# MCU.net
KiCad netlist of a schematic drawn in Altium Designer
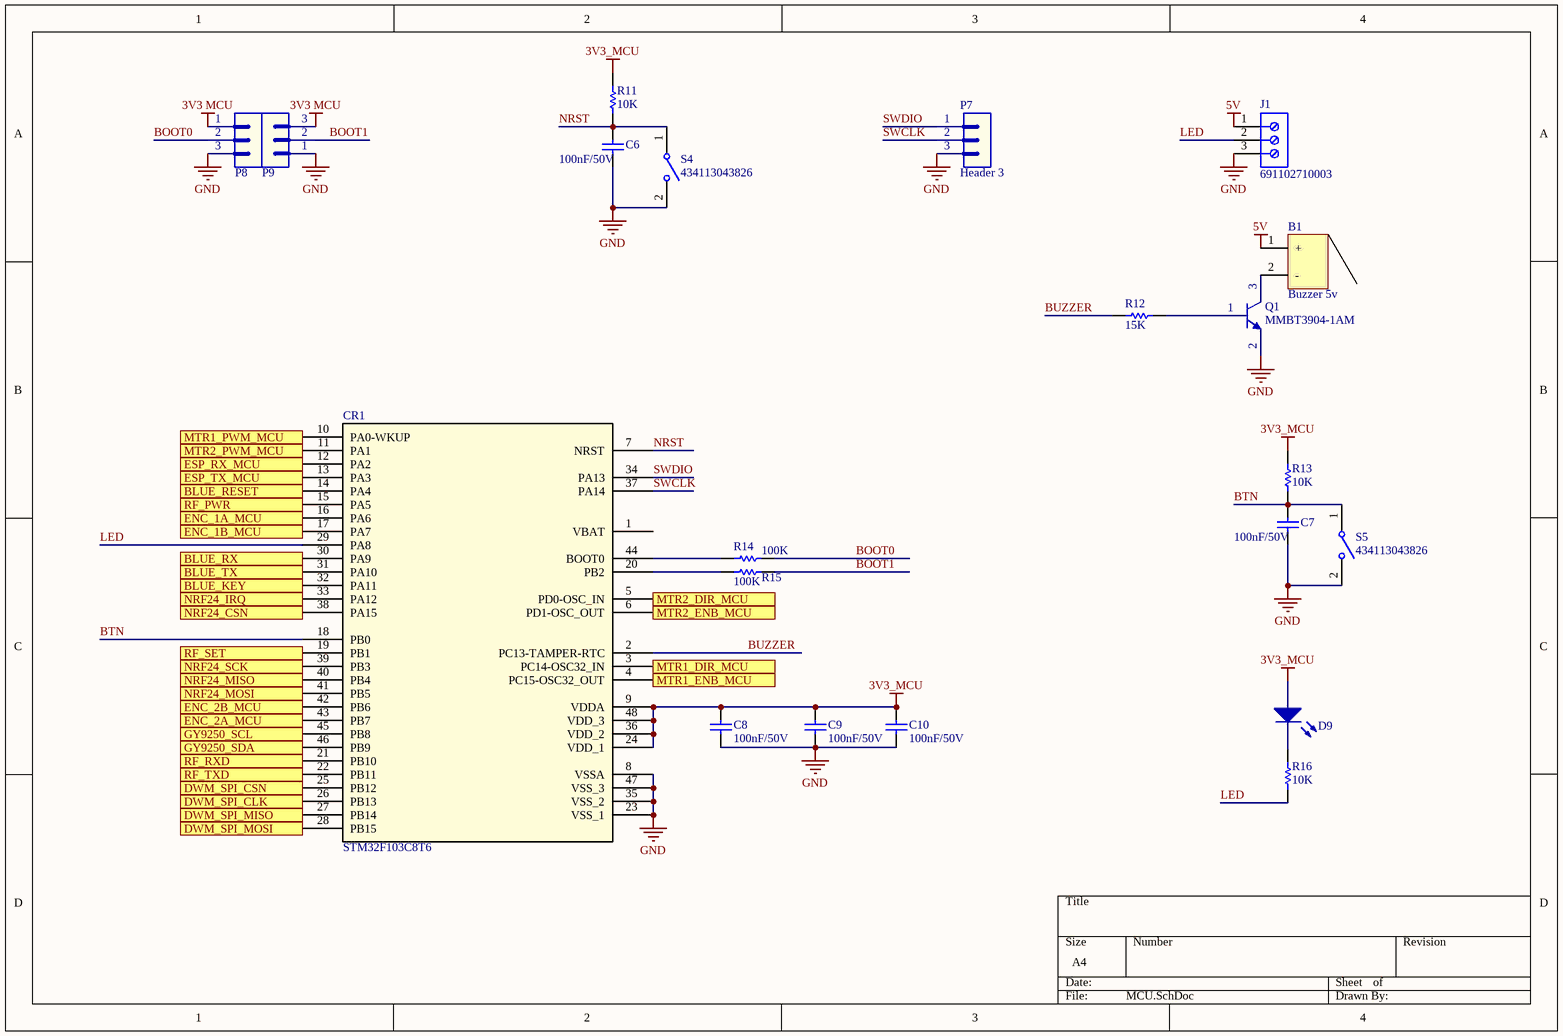
[diagram p0: MCU.SchDoc]

(export (version "E")
  (design (tool "Eeschema 10.0.6"))
  (components
    (comp (ref "B1") (value "Buzzer 5v") (footprint "Buzzer 5v") (libsource (lib "Stm32") (part "Buzzer 5v")))
    (comp (ref "C6")
      (value "100nF/50V")
      (footprint "CAP-SM-0805")
      (description "CAP CER 1000PF 100V X7R 0805")
      (fields
        (field (name "MANUFACTURER") "Johanson Dielectrics Inc.")
        (field (name "MANUFACTURER PART NUMBER") "101X15W102MV4E")
      )
      (libsource (lib "Capacitor") (part "Cap-1nF-50V-0805"))
    )
    (comp (ref "C7")
      (value "100nF/50V")
      (footprint "CAP-SM-0805")
      (description "CAP CER 1000PF 100V X7R 0805")
      (fields
        (field (name "MANUFACTURER") "Johanson Dielectrics Inc.")
        (field (name "MANUFACTURER PART NUMBER") "101X15W102MV4E")
      )
      (libsource (lib "Capacitor") (part "Cap-1nF-50V-0805"))
    )
    (comp (ref "C8")
      (value "100nF/50V")
      (footprint "CAP-SM-0805")
      (description "CAP CER 1000PF 100V X7R 0805")
      (fields
        (field (name "MANUFACTURER") "Johanson Dielectrics Inc.")
        (field (name "MANUFACTURER PART NUMBER") "101X15W102MV4E")
      )
      (libsource (lib "Capacitor") (part "Cap-1nF-50V-0805"))
    )
    (comp (ref "C9")
      (value "100nF/50V")
      (footprint "CAP-SM-0805")
      (description "CAP CER 1000PF 100V X7R 0805")
      (fields
        (field (name "MANUFACTURER") "Johanson Dielectrics Inc.")
        (field (name "MANUFACTURER PART NUMBER") "101X15W102MV4E")
      )
      (libsource (lib "Capacitor") (part "Cap-1nF-50V-0805"))
    )
    (comp (ref "C10")
      (value "100nF/50V")
      (footprint "CAP-SM-0805")
      (description "CAP CER 1000PF 100V X7R 0805")
      (fields
        (field (name "MANUFACTURER") "Johanson Dielectrics Inc.")
        (field (name "MANUFACTURER PART NUMBER") "101X15W102MV4E")
      )
      (libsource (lib "Capacitor") (part "Cap-1nF-50V-0805"))
    )
    (comp (ref "CR1")
      (value "STM32F103C8T6")
      (footprint "STM32F103C8T6")
      (fields (field (name "COPYRIGHT") "Copyright (C) 2018 Accelerated Designs. All rights reserved"))
      (libsource (lib "Schlib1") (part "STM32F103C8T6"))
    )
    (comp (ref "D9") (value "LED") (footprint "LED_0603_Blue") (libsource (lib "PIF_C16_lib") (part "LED")))
    (comp (ref "J1")
      (value "691102710003")
      (footprint "691102710003")
      (description "WR-TBL Serie 102 Horizontal Entry Modular, Pressure Clamp, pitch 5mm, 3p")
      (fields (field (name "PUBLISHER") "Wurth Elektronik"))
      (libsource (lib "691101710002_Altium_WR-TBL_rev19a") (part "691102710003"))
    )
    (comp (ref "P7")
      (value "Header 3")
      (footprint "jp3")
      (description "Header, 3-Pin")
      (fields (field (name "PUBLISHER") "Altium Limited"))
      (libsource (lib "") (part "Header 3_1"))
    )
    (comp (ref "P8")
      (value "~")
      (footprint "jp3")
      (description "Header, 3-Pin")
      (fields (field (name "PUBLISHER") "Altium Limited"))
      (libsource (lib "") (part "Header 3_1"))
    )
    (comp (ref "P9")
      (value "~")
      (footprint "jp3")
      (description "Header, 3-Pin")
      (fields (field (name "PUBLISHER") "Altium Limited"))
      (libsource (lib "Integrated_Library_Test") (part "Header 3"))
    )
    (comp (ref "Q1")
      (value "MMBT3904-1AM")
      (footprint "SOT23_NEX")
      (libsource (lib "BJT") (part "MMBT3904-1AM"))
    )
    (comp (ref "R11")
      (value "10K")
      (footprint "Resistor:RES-SM-0805")
      (description "RES 0 OHM JUMPER 0805")
      (fields
        (field (name "MANUFACTURER") "Vishay Dale")
        (field (name "MANUFACTURER PART NUMBER") "WSL080500000ZEA9")
      )
      (libsource (lib "Resistor") (part "Res-0-0805"))
    )
    (comp (ref "R12")
      (value "15K")
      (footprint "Resistor:RES-SM-0805")
      (description "RES 12 KOHM JUMPER 0805")
      (fields
        (field (name "MANUFACTURER") "Vishay Thin Film")
        (field (name "MANUFACTURER PART NUMBER") "PAT0805E3121BST1")
      )
      (libsource (lib "Resistor") (part "Res-12K-0805"))
    )
    (comp (ref "R13")
      (value "10K")
      (footprint "Resistor:RES-SM-0805")
      (description "RES 0 OHM JUMPER 0805")
      (fields
        (field (name "MANUFACTURER") "Vishay Dale")
        (field (name "MANUFACTURER PART NUMBER") "WSL080500000ZEA9")
      )
      (libsource (lib "Resistor") (part "Res-0-0805"))
    )
    (comp (ref "R14")
      (value "100K")
      (footprint "Resistor:RES-SM-0805")
      (description "RES 1K OHM 1% 1/4W 0805")
      (fields
        (field (name "MANUFACTURER") "Stackpole Electronics Inc")
        (field (name "MANUFACTURER PART NUMBER") "RNCP0805FTD1K00")
      )
      (libsource (lib "Resistor") (part "Res-1K-0805"))
    )
    (comp (ref "R15")
      (value "100K")
      (footprint "Resistor:RES-SM-0805")
      (description "RES 1K OHM 1% 1/4W 0805")
      (fields
        (field (name "MANUFACTURER") "Stackpole Electronics Inc")
        (field (name "MANUFACTURER PART NUMBER") "RNCP0805FTD1K00")
      )
      (libsource (lib "Resistor") (part "Res-1K-0805"))
    )
    (comp (ref "R16")
      (value "10K")
      (footprint "Resistor:RES-SM-0805")
      (description "RES 0 OHM JUMPER 0805")
      (fields
        (field (name "MANUFACTURER") "Vishay Dale")
        (field (name "MANUFACTURER PART NUMBER") "WSL080500000ZEA9")
      )
      (libsource (lib "Resistor") (part "Res-0-0805"))
    )
    (comp (ref "S4")
      (value "434113043826")
      (footprint "434113043826")
      (description "WS-TASV J-Bend SMT Tact Switch 6x3.5mm, height 4.3mm, 260gf")
      (fields (field (name "PUBLISHER") "Wurth Elektronik"))
      (libsource (lib "434113043826_Altium_WS-TASV_rev20a") (part "434113043826"))
    )
    (comp (ref "S5")
      (value "434113043826")
      (footprint "434113043826")
      (description "WS-TASV J-Bend SMT Tact Switch 6x3.5mm, height 4.3mm, 260gf")
      (fields (field (name "PUBLISHER") "Wurth Elektronik"))
      (libsource (lib "434113043826_Altium_WS-TASV_rev20a") (part "434113043826"))
    )
  )
  (nets
    (net (code "1") (name "/BLUE_KEY") (class "Default")
      (node (ref "CR1") (pin "32") (pinfunction "PA11_32") (pintype "open_collector"))
    )
    (net (code "2") (name "/BLUE_RESET") (class "Default")
      (node (ref "CR1") (pin "14") (pinfunction "PA4_14") (pintype "open_collector"))
    )
    (net (code "3") (name "/BLUE_RX") (class "Default")
      (node (ref "CR1") (pin "30") (pinfunction "PA9_30") (pintype "open_collector"))
    )
    (net (code "4") (name "/BLUE_TX") (class "Default")
      (node (ref "CR1") (pin "31") (pinfunction "PA10_31") (pintype "open_collector"))
    )
    (net (code "5") (name "/BOOT0") (class "Default")
      (node (ref "P8") (pin "2") (pinfunction "2_2") (pintype "passive"))
      (node (ref "R14") (pin "2") (pinfunction "2_2") (pintype "passive"))
    )
    (net (code "6") (name "/BOOT1") (class "Default")
      (node (ref "P9") (pin "2") (pinfunction "2_2") (pintype "passive"))
      (node (ref "R15") (pin "2") (pinfunction "2_2") (pintype "passive"))
    )
    (net (code "7") (name "/BTN") (class "Default")
      (node (ref "C7") (pin "2") (pinfunction "2_2") (pintype "passive"))
      (node (ref "CR1") (pin "18") (pinfunction "PB0_18") (pintype "open_collector"))
      (node (ref "R13") (pin "1") (pinfunction "1_1") (pintype "passive"))
      (node (ref "S5") (pin "1") (pinfunction "1_1") (pintype "passive"))
    )
    (net (code "8") (name "/BUZZER") (class "Default")
      (node (ref "CR1") (pin "2") (pinfunction "PC13-TAMPER-RTC_2") (pintype "open_collector"))
      (node (ref "R12") (pin "1") (pinfunction "1_1") (pintype "passive"))
    )
    (net (code "9") (name "/DWM_SPI_CLK") (class "Default")
      (node (ref "CR1") (pin "26") (pinfunction "PB13_26") (pintype "open_collector"))
    )
    (net (code "10") (name "/DWM_SPI_CSN") (class "Default")
      (node (ref "CR1") (pin "25") (pinfunction "PB12_25") (pintype "open_collector"))
    )
    (net (code "11") (name "/DWM_SPI_MISO") (class "Default")
      (node (ref "CR1") (pin "27") (pinfunction "PB14_27") (pintype "open_collector"))
    )
    (net (code "12") (name "/DWM_SPI_MOSI") (class "Default")
      (node (ref "CR1") (pin "28") (pinfunction "PB15_28") (pintype "open_collector"))
    )
    (net (code "13") (name "/ENC_1A_MCU") (class "Default")
      (node (ref "CR1") (pin "16") (pinfunction "PA6_16") (pintype "open_collector"))
    )
    (net (code "14") (name "/ENC_1B_MCU") (class "Default")
      (node (ref "CR1") (pin "17") (pinfunction "PA7_17") (pintype "open_collector"))
    )
    (net (code "15") (name "/ENC_2A_MCU") (class "Default")
      (node (ref "CR1") (pin "43") (pinfunction "PB7_43") (pintype "open_collector"))
    )
    (net (code "16") (name "/ENC_2B_MCU") (class "Default")
      (node (ref "CR1") (pin "42") (pinfunction "PB6_42") (pintype "open_collector"))
    )
    (net (code "17") (name "/ESP_RX_MCU") (class "Default")
      (node (ref "CR1") (pin "12") (pinfunction "PA2_12") (pintype "open_collector"))
    )
    (net (code "18") (name "/ESP_TX_MCU") (class "Default")
      (node (ref "CR1") (pin "13") (pinfunction "PA3_13") (pintype "open_collector"))
    )
    (net (code "19") (name "/GY9250_SCL") (class "Default")
      (node (ref "CR1") (pin "45") (pinfunction "PB8_45") (pintype "open_collector"))
    )
    (net (code "20") (name "/GY9250_SDA") (class "Default")
      (node (ref "CR1") (pin "46") (pinfunction "PB9_46") (pintype "open_collector"))
    )
    (net (code "21") (name "/LED") (class "Default")
      (node (ref "CR1") (pin "29") (pinfunction "PA8_29") (pintype "open_collector"))
      (node (ref "J1") (pin "2") (pinfunction "2_2") (pintype "passive"))
      (node (ref "R16") (pin "1") (pinfunction "1_1") (pintype "passive"))
    )
    (net (code "22") (name "/MTR1_DIR_MCU") (class "Default")
      (node (ref "CR1") (pin "3") (pinfunction "PC14-OSC32_IN_3") (pintype "open_collector"))
    )
    (net (code "23") (name "/MTR1_ENB_MCU") (class "Default")
      (node (ref "CR1") (pin "4") (pinfunction "PC15-OSC32_OUT_4") (pintype "open_collector"))
    )
    (net (code "24") (name "/MTR1_PWM_MCU") (class "Default")
      (node (ref "CR1") (pin "10") (pinfunction "PA0-WKUP_10") (pintype "open_collector"))
    )
    (net (code "25") (name "/MTR2_DIR_MCU") (class "Default")
      (node (ref "CR1") (pin "5") (pinfunction "PD0-OSC_IN_5") (pintype "open_collector"))
    )
    (net (code "26") (name "/MTR2_ENB_MCU") (class "Default")
      (node (ref "CR1") (pin "6") (pinfunction "PD1-OSC_OUT_6") (pintype "open_collector"))
    )
    (net (code "27") (name "/MTR2_PWM_MCU") (class "Default")
      (node (ref "CR1") (pin "11") (pinfunction "PA1_11") (pintype "open_collector"))
    )
    (net (code "28") (name "/NRF24_CSN") (class "Default")
      (node (ref "CR1") (pin "38") (pinfunction "PA15_38") (pintype "open_collector"))
    )
    (net (code "29") (name "/NRF24_IRQ") (class "Default")
      (node (ref "CR1") (pin "33") (pinfunction "PA12_33") (pintype "open_collector"))
    )
    (net (code "30") (name "/NRF24_MISO") (class "Default")
      (node (ref "CR1") (pin "40") (pinfunction "PB4_40") (pintype "open_collector"))
    )
    (net (code "31") (name "/NRF24_MOSI") (class "Default")
      (node (ref "CR1") (pin "41") (pinfunction "PB5_41") (pintype "open_collector"))
    )
    (net (code "32") (name "/NRF24_SCK") (class "Default")
      (node (ref "CR1") (pin "39") (pinfunction "PB3_39") (pintype "open_collector"))
    )
    (net (code "33") (name "/NRST") (class "Default")
      (node (ref "C6") (pin "2") (pinfunction "2_2") (pintype "passive"))
      (node (ref "CR1") (pin "7") (pinfunction "NRST_7") (pintype "open_collector"))
      (node (ref "R11") (pin "1") (pinfunction "1_1") (pintype "passive"))
      (node (ref "S4") (pin "1") (pinfunction "1_1") (pintype "passive"))
    )
    (net (code "34") (name "/RF_PWR") (class "Default")
      (node (ref "CR1") (pin "15") (pinfunction "PA5_15") (pintype "open_collector"))
    )
    (net (code "35") (name "/RF_RXD") (class "Default")
      (node (ref "CR1") (pin "21") (pinfunction "PB10_21") (pintype "open_collector"))
    )
    (net (code "36") (name "/RF_SET") (class "Default")
      (node (ref "CR1") (pin "19") (pinfunction "PB1_19") (pintype "open_collector"))
    )
    (net (code "37") (name "/RF_TXD") (class "Default")
      (node (ref "CR1") (pin "22") (pinfunction "PB11_22") (pintype "open_collector"))
    )
    (net (code "38") (name "/SWCLK") (class "Default")
      (node (ref "CR1") (pin "37") (pinfunction "PA14_37") (pintype "open_collector"))
      (node (ref "P7") (pin "2") (pinfunction "2_2") (pintype "passive"))
    )
    (net (code "39") (name "/SWDIO") (class "Default")
      (node (ref "CR1") (pin "34") (pinfunction "PA13_34") (pintype "open_collector"))
      (node (ref "P7") (pin "1") (pinfunction "1_1") (pintype "passive"))
    )
    (net (code "40") (name "3V3 MCU") (class "Default")
      (node (ref "P8") (pin "1") (pinfunction "1_1") (pintype "passive"))
      (node (ref "P9") (pin "3") (pinfunction "3_3") (pintype "passive"))
    )
    (net (code "41") (name "3V3_MCU") (class "Default")
      (node (ref "C10") (pin "2") (pinfunction "2_2") (pintype "passive"))
      (node (ref "C8") (pin "2") (pinfunction "2_2") (pintype "passive"))
      (node (ref "C9") (pin "2") (pinfunction "2_2") (pintype "passive"))
      (node (ref "CR1") (pin "24") (pinfunction "VDD_1_24") (pintype "open_collector"))
      (node (ref "CR1") (pin "36") (pinfunction "VDD_2_36") (pintype "open_collector"))
      (node (ref "CR1") (pin "48") (pinfunction "VDD_3_48") (pintype "open_collector"))
      (node (ref "CR1") (pin "9") (pinfunction "VDDA_9") (pintype "open_collector"))
      (node (ref "D9") (pin "1") (pinfunction "A_1") (pintype "passive"))
      (node (ref "R11") (pin "2") (pinfunction "2_2") (pintype "passive"))
      (node (ref "R13") (pin "2") (pinfunction "2_2") (pintype "passive"))
    )
    (net (code "42") (name "5V") (class "Default")
      (node (ref "B1") (pin "1") (pinfunction "+_1") (pintype "passive"))
      (node (ref "J1") (pin "1") (pinfunction "1_1") (pintype "passive"))
    )
    (net (code "43") (name "GND") (class "Default")
      (node (ref "C10") (pin "1") (pinfunction "1_1") (pintype "passive"))
      (node (ref "C6") (pin "1") (pinfunction "1_1") (pintype "passive"))
      (node (ref "C7") (pin "1") (pinfunction "1_1") (pintype "passive"))
      (node (ref "C8") (pin "1") (pinfunction "1_1") (pintype "passive"))
      (node (ref "C9") (pin "1") (pinfunction "1_1") (pintype "passive"))
      (node (ref "CR1") (pin "23") (pinfunction "VSS_1_23") (pintype "open_collector"))
      (node (ref "CR1") (pin "35") (pinfunction "VSS_2_35") (pintype "open_collector"))
      (node (ref "CR1") (pin "47") (pinfunction "VSS_3_47") (pintype "open_collector"))
      (node (ref "CR1") (pin "8") (pinfunction "VSSA_8") (pintype "open_collector"))
      (node (ref "J1") (pin "3") (pinfunction "3_3") (pintype "passive"))
      (node (ref "P7") (pin "3") (pinfunction "3_3") (pintype "passive"))
      (node (ref "P8") (pin "3") (pinfunction "3_3") (pintype "passive"))
      (node (ref "P9") (pin "1") (pinfunction "1_1") (pintype "passive"))
      (node (ref "Q1") (pin "2") (pinfunction "E_2") (pintype "passive"))
      (node (ref "S4") (pin "2") (pinfunction "2_2") (pintype "passive"))
      (node (ref "S5") (pin "2") (pinfunction "2_2") (pintype "passive"))
    )
    (net (code "44") (name "Net-(B1--)") (class "Default")
      (node (ref "B1") (pin "2") (pinfunction "-_2") (pintype "passive"))
      (node (ref "Q1") (pin "3") (pinfunction "C_3") (pintype "passive"))
    )
    (net (code "45") (name "Net-(CR1-BOOT0)") (class "Default")
      (node (ref "CR1") (pin "44") (pinfunction "BOOT0_44") (pintype "open_collector"))
      (node (ref "R14") (pin "1") (pinfunction "1_1") (pintype "passive"))
    )
    (net (code "46") (name "Net-(CR1-PB2)") (class "Default")
      (node (ref "CR1") (pin "20") (pinfunction "PB2_20") (pintype "open_collector"))
      (node (ref "R15") (pin "1") (pinfunction "1_1") (pintype "passive"))
    )
    (net (code "47") (name "Net-(D9-K)") (class "Default")
      (node (ref "D9") (pin "2") (pinfunction "K_2") (pintype "passive"))
      (node (ref "R16") (pin "2") (pinfunction "2_2") (pintype "passive"))
    )
    (net (code "48") (name "Net-(Q1-B)") (class "Default")
      (node (ref "Q1") (pin "1") (pinfunction "B_1") (pintype "passive"))
      (node (ref "R12") (pin "2") (pinfunction "2_2") (pintype "passive"))
    )
    (net (code "49") (name "unconnected-(CR1-VBAT-Pad1)") (class "Default")
      (node (ref "CR1") (pin "1") (pinfunction "VBAT_1") (pintype "open_collector"))
    )
  )
)
